# teensy_ms.net
KiCad netlist of a schematic drawn in EAGLE
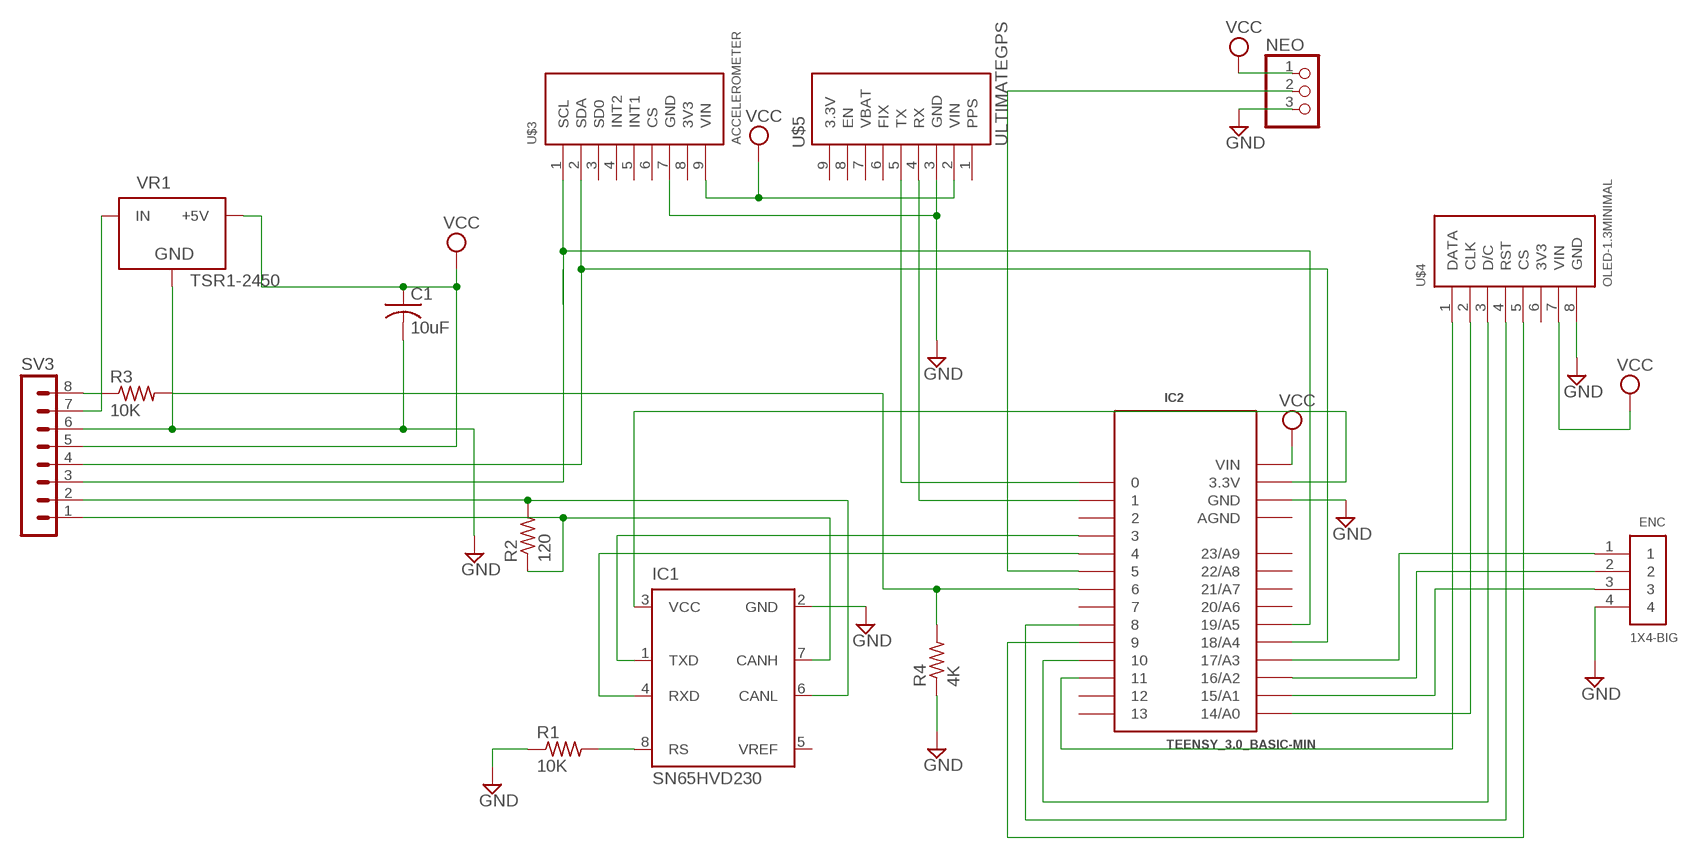
[diagram p0: schematic, sheet 1]

(export (version "E")
  (design (tool "Eeschema 10.0.6"))
  (components
    (comp (ref "C1")
      (value "10uF")
      (footprint "eagle-import:C1206")
      (libsource (lib "eagle-import") (part "C-USC1206"))
    )
    (comp (ref "ENC")
      (value "1X4-BIG")
      (footprint "eagle-import:1X04-BIG")
      (libsource (lib "eagle-import") (part "1X4-BIG"))
    )
    (comp (ref "IC1")
      (value "SN65HVD230")
      (footprint "eagle-import:SO8")
      (libsource (lib "eagle-import") (part "SN65HVD230"))
    )
    (comp (ref "IC2")
      (value "TEENSY_3.0_BASIC-MIN")
      (footprint "eagle-import:TEESNY_3.0_BASIC-MIN")
      (libsource (lib "eagle-import") (part "TEENSY_3.0_BASIC-MIN"))
    )
    (comp (ref "NEO")
      (value "PINHD-1X3")
      (footprint "eagle-import:1X03")
      (libsource (lib "eagle-import") (part "PINHD-1X3"))
    )
    (comp (ref "R1")
      (value "10K")
      (footprint "eagle-import:M1206")
      (libsource (lib "eagle-import") (part "R-US_M1206"))
    )
    (comp (ref "R2")
      (value "120")
      (footprint "eagle-import:M1206")
      (libsource (lib "eagle-import") (part "R-US_M1206"))
    )
    (comp (ref "R3")
      (value "10K")
      (footprint "eagle-import:M1206")
      (libsource (lib "eagle-import") (part "R-US_M1206"))
    )
    (comp (ref "R4")
      (value "4K")
      (footprint "eagle-import:M1206")
      (libsource (lib "eagle-import") (part "R-US_M1206"))
    )
    (comp (ref "SV3")
      (value "MA08-1")
      (footprint "eagle-import:MA08-1")
      (libsource (lib "eagle-import") (part "MA08-1"))
    )
    (comp (ref "U$3")
      (value "ACCELEROMETER")
      (footprint "eagle-import:ACCELEROMETER")
      (libsource (lib "eagle-import") (part "ACCELEROMETER"))
    )
    (comp (ref "U$4")
      (value "OLED-1.3MINIMAL")
      (footprint "eagle-import:OLED-1.3-BARE")
      (libsource (lib "eagle-import") (part "OLED-1.3MINIMAL"))
    )
    (comp (ref "U$5")
      (value "ULTIMATEGPS")
      (footprint "eagle-import:ULTIMATEGPS")
      (libsource (lib "eagle-import") (part "ULTIMATEGPS"))
    )
    (comp (ref "VR1")
      (value "TSR1-2450")
      (footprint "eagle-import:TSR-1")
      (libsource (lib "eagle-import") (part "TSR1-2450"))
    )
  )
  (nets
    (net (code "1") (name "/AGND") (class "Default")
      (node (ref "IC2") (pin "AGND") (pinfunction "AGND_AGND") (pintype "power_in"))
    )
    (net (code "2") (name "GND") (class "Default")
      (node (ref "C1") (pin "2") (pinfunction "2_2") (pintype "passive"))
      (node (ref "ENC") (pin "4") (pinfunction "4_4") (pintype "bidirectional"))
      (node (ref "IC1") (pin "2") (pinfunction "GND_2") (pintype "power_in"))
      (node (ref "IC2") (pin "GND") (pinfunction "GND_GND") (pintype "power_in"))
      (node (ref "NEO") (pin "3") (pinfunction "3_3") (pintype "passive"))
      (node (ref "R1") (pin "1") (pinfunction "1_1") (pintype "passive"))
      (node (ref "R4") (pin "1") (pinfunction "1_1") (pintype "passive"))
      (node (ref "SV3") (pin "6") (pinfunction "6_6") (pintype "passive"))
      (node (ref "U$3") (pin "7") (pinfunction "GND_7") (pintype "bidirectional"))
      (node (ref "U$4") (pin "8") (pinfunction "GND_8") (pintype "bidirectional"))
      (node (ref "U$5") (pin "3") (pinfunction "GND_3") (pintype "bidirectional"))
      (node (ref "VR1") (pin "2") (pinfunction "GND_2") (pintype "power_in"))
    )
    (net (code "3") (name "Net-(ENC-Pad1)") (class "Default")
      (node (ref "ENC") (pin "1") (pinfunction "1_1") (pintype "bidirectional"))
      (node (ref "IC2") (pin "17/A3") (pinfunction "17/A3_17/A3") (pintype "bidirectional"))
    )
    (net (code "4") (name "Net-(ENC-Pad2)") (class "Default")
      (node (ref "ENC") (pin "2") (pinfunction "2_2") (pintype "bidirectional"))
      (node (ref "IC2") (pin "16/A2") (pinfunction "16/A2_16/A2") (pintype "bidirectional"))
    )
    (net (code "5") (name "Net-(ENC-Pad3)") (class "Default")
      (node (ref "ENC") (pin "3") (pinfunction "3_3") (pintype "bidirectional"))
      (node (ref "IC2") (pin "15/A1") (pinfunction "15/A1_15/A1") (pintype "bidirectional"))
    )
    (net (code "6") (name "Net-(IC1-CANH)") (class "Default")
      (node (ref "IC1") (pin "7") (pinfunction "CANH_7") (pintype "bidirectional"))
      (node (ref "R2") (pin "1") (pinfunction "1_1") (pintype "passive"))
      (node (ref "SV3") (pin "1") (pinfunction "1_1") (pintype "passive"))
    )
    (net (code "7") (name "Net-(IC1-CANL)") (class "Default")
      (node (ref "IC1") (pin "6") (pinfunction "CANL_6") (pintype "bidirectional"))
      (node (ref "R2") (pin "2") (pinfunction "2_2") (pintype "passive"))
      (node (ref "SV3") (pin "2") (pinfunction "2_2") (pintype "passive"))
    )
    (net (code "8") (name "Net-(IC1-RS)") (class "Default")
      (node (ref "IC1") (pin "8") (pinfunction "RS_8") (pintype "input"))
      (node (ref "R1") (pin "2") (pinfunction "2_2") (pintype "passive"))
    )
    (net (code "9") (name "Net-(IC1-RXD)") (class "Default")
      (node (ref "IC1") (pin "4") (pinfunction "RXD_4") (pintype "output"))
      (node (ref "IC2") (pin "4") (pinfunction "4_4") (pintype "bidirectional"))
    )
    (net (code "10") (name "Net-(IC1-TXD)") (class "Default")
      (node (ref "IC1") (pin "1") (pinfunction "TXD_1") (pintype "input"))
      (node (ref "IC2") (pin "3") (pinfunction "3_3") (pintype "bidirectional"))
    )
    (net (code "11") (name "Net-(IC1-VCC)") (class "Default")
      (node (ref "IC1") (pin "3") (pinfunction "VCC_3") (pintype "power_in"))
      (node (ref "IC2") (pin "3.3V") (pinfunction "3.3V_3.3V") (pintype "power_in"))
    )
    (net (code "12") (name "Net-(IC2-Pad5)") (class "Default")
      (node (ref "IC2") (pin "5") (pinfunction "5_5") (pintype "bidirectional"))
      (node (ref "NEO") (pin "2") (pinfunction "2_2") (pintype "passive"))
    )
    (net (code "13") (name "Net-(IC2-Pad6)") (class "Default")
      (node (ref "IC2") (pin "6") (pinfunction "6_6") (pintype "bidirectional"))
      (node (ref "R3") (pin "2") (pinfunction "2_2") (pintype "passive"))
      (node (ref "R4") (pin "2") (pinfunction "2_2") (pintype "passive"))
    )
    (net (code "14") (name "Net-(R3-Pad1)") (class "Default")
      (node (ref "R3") (pin "1") (pinfunction "1_1") (pintype "passive"))
      (node (ref "SV3") (pin "8") (pinfunction "8_8") (pintype "passive"))
    )
    (net (code "15") (name "Net-(U$3-SCL)") (class "Default")
      (node (ref "IC2") (pin "19/A5") (pinfunction "19/A5_19/A5") (pintype "bidirectional"))
      (node (ref "SV3") (pin "3") (pinfunction "3_3") (pintype "passive"))
      (node (ref "U$3") (pin "1") (pinfunction "SCL_1") (pintype "bidirectional"))
    )
    (net (code "16") (name "Net-(U$3-SDA)") (class "Default")
      (node (ref "IC2") (pin "18/A4") (pinfunction "18/A4_18/A4") (pintype "bidirectional"))
      (node (ref "SV3") (pin "4") (pinfunction "4_4") (pintype "passive"))
      (node (ref "U$3") (pin "2") (pinfunction "SDA_2") (pintype "bidirectional"))
    )
    (net (code "17") (name "Net-(U$4-CLK)") (class "Default")
      (node (ref "IC2") (pin "14/A0") (pinfunction "14/A0_14/A0") (pintype "bidirectional"))
      (node (ref "U$4") (pin "2") (pinfunction "CLK_2") (pintype "bidirectional"))
    )
    (net (code "18") (name "Net-(U$4-CS)") (class "Default")
      (node (ref "IC2") (pin "9") (pinfunction "9_9") (pintype "bidirectional"))
      (node (ref "U$4") (pin "5") (pinfunction "CS_5") (pintype "bidirectional"))
    )
    (net (code "19") (name "Net-(U$4-DATA)") (class "Default")
      (node (ref "IC2") (pin "11") (pinfunction "11_11") (pintype "bidirectional"))
      (node (ref "U$4") (pin "1") (pinfunction "DATA_1") (pintype "bidirectional"))
    )
    (net (code "20") (name "Net-(U$4-D{slash}C)") (class "Default")
      (node (ref "IC2") (pin "10") (pinfunction "10_10") (pintype "bidirectional"))
      (node (ref "U$4") (pin "3") (pinfunction "D/C_3") (pintype "bidirectional"))
    )
    (net (code "21") (name "Net-(U$4-RST)") (class "Default")
      (node (ref "IC2") (pin "8") (pinfunction "8_8") (pintype "bidirectional"))
      (node (ref "U$4") (pin "4") (pinfunction "RST_4") (pintype "bidirectional"))
    )
    (net (code "22") (name "Net-(U$5-RX)") (class "Default")
      (node (ref "IC2") (pin "1") (pinfunction "1_1") (pintype "bidirectional"))
      (node (ref "U$5") (pin "4") (pinfunction "RX_4") (pintype "bidirectional"))
    )
    (net (code "23") (name "Net-(U$5-TX)") (class "Default")
      (node (ref "IC2") (pin "0") (pinfunction "0_0") (pintype "bidirectional"))
      (node (ref "U$5") (pin "5") (pinfunction "TX_5") (pintype "bidirectional"))
    )
    (net (code "24") (name "Net-(VR1-IN)") (class "Default")
      (node (ref "SV3") (pin "7") (pinfunction "7_7") (pintype "passive"))
      (node (ref "VR1") (pin "1") (pinfunction "IN_1") (pintype "power_in"))
    )
    (net (code "25") (name "VCC") (class "Default")
      (node (ref "C1") (pin "1") (pinfunction "1_1") (pintype "passive"))
      (node (ref "IC2") (pin "VIN") (pinfunction "VIN_VIN") (pintype "power_in"))
      (node (ref "NEO") (pin "1") (pinfunction "1_1") (pintype "passive"))
      (node (ref "SV3") (pin "5") (pinfunction "5_5") (pintype "passive"))
      (node (ref "U$3") (pin "9") (pinfunction "VIN_9") (pintype "bidirectional"))
      (node (ref "U$4") (pin "7") (pinfunction "VIN_7") (pintype "bidirectional"))
      (node (ref "U$5") (pin "2") (pinfunction "VIN_2") (pintype "bidirectional"))
      (node (ref "VR1") (pin "3") (pinfunction "+5V_3") (pintype "power_in"))
    )
    (net (code "26") (name "unconnected-(IC1-VREF-Pad5)") (class "Default")
      (node (ref "IC1") (pin "5") (pinfunction "VREF_5") (pintype "output"))
    )
    (net (code "27") (name "unconnected-(IC2-Pad2)") (class "Default")
      (node (ref "IC2") (pin "2") (pinfunction "2_2") (pintype "bidirectional"))
    )
    (net (code "28") (name "unconnected-(IC2-Pad7)") (class "Default")
      (node (ref "IC2") (pin "7") (pinfunction "7_7") (pintype "bidirectional"))
    )
    (net (code "29") (name "unconnected-(IC2-Pad12)") (class "Default")
      (node (ref "IC2") (pin "12") (pinfunction "12_12") (pintype "bidirectional"))
    )
    (net (code "30") (name "unconnected-(IC2-Pad13)") (class "Default")
      (node (ref "IC2") (pin "13") (pinfunction "13_13") (pintype "bidirectional"))
    )
    (net (code "31") (name "unconnected-(IC2-Pad20{slash}A6)") (class "Default")
      (node (ref "IC2") (pin "20/A6") (pinfunction "20/A6_20/A6") (pintype "bidirectional"))
    )
    (net (code "32") (name "unconnected-(IC2-Pad21{slash}A7)") (class "Default")
      (node (ref "IC2") (pin "21/A7") (pinfunction "21/A7_21/A7") (pintype "bidirectional"))
    )
    (net (code "33") (name "unconnected-(IC2-Pad22{slash}A8)") (class "Default")
      (node (ref "IC2") (pin "22/A8") (pinfunction "22/A8_22/A8") (pintype "bidirectional"))
    )
    (net (code "34") (name "unconnected-(IC2-Pad23{slash}A9)") (class "Default")
      (node (ref "IC2") (pin "23/A9") (pinfunction "23/A9_23/A9") (pintype "bidirectional"))
    )
    (net (code "35") (name "unconnected-(U$3-3V3-Pad8)") (class "Default")
      (node (ref "U$3") (pin "8") (pinfunction "3V3_8") (pintype "bidirectional"))
    )
    (net (code "36") (name "unconnected-(U$3-CS-Pad6)") (class "Default")
      (node (ref "U$3") (pin "6") (pinfunction "CS_6") (pintype "bidirectional"))
    )
    (net (code "37") (name "unconnected-(U$3-INT1-Pad5)") (class "Default")
      (node (ref "U$3") (pin "5") (pinfunction "INT1_5") (pintype "bidirectional"))
    )
    (net (code "38") (name "unconnected-(U$3-INT2-Pad4)") (class "Default")
      (node (ref "U$3") (pin "4") (pinfunction "INT2_4") (pintype "bidirectional"))
    )
    (net (code "39") (name "unconnected-(U$3-SD0-Pad3)") (class "Default")
      (node (ref "U$3") (pin "3") (pinfunction "SD0_3") (pintype "bidirectional"))
    )
    (net (code "40") (name "unconnected-(U$4-3V3-Pad6)") (class "Default")
      (node (ref "U$4") (pin "6") (pinfunction "3V3_6") (pintype "bidirectional"))
    )
    (net (code "41") (name "unconnected-(U$5-3.3V-Pad9)") (class "Default")
      (node (ref "U$5") (pin "9") (pinfunction "3.3V_9") (pintype "bidirectional"))
    )
    (net (code "42") (name "unconnected-(U$5-EN-Pad8)") (class "Default")
      (node (ref "U$5") (pin "8") (pinfunction "EN_8") (pintype "bidirectional"))
    )
    (net (code "43") (name "unconnected-(U$5-FIX-Pad6)") (class "Default")
      (node (ref "U$5") (pin "6") (pinfunction "FIX_6") (pintype "bidirectional"))
    )
    (net (code "44") (name "unconnected-(U$5-PPS-Pad1)") (class "Default")
      (node (ref "U$5") (pin "1") (pinfunction "PPS_1") (pintype "bidirectional"))
    )
    (net (code "45") (name "unconnected-(U$5-VBAT-Pad7)") (class "Default")
      (node (ref "U$5") (pin "7") (pinfunction "VBAT_7") (pintype "bidirectional"))
    )
  )
)
